# UltraSoundLightConfig.net
KiCad netlist of a schematic drawn in EAGLE
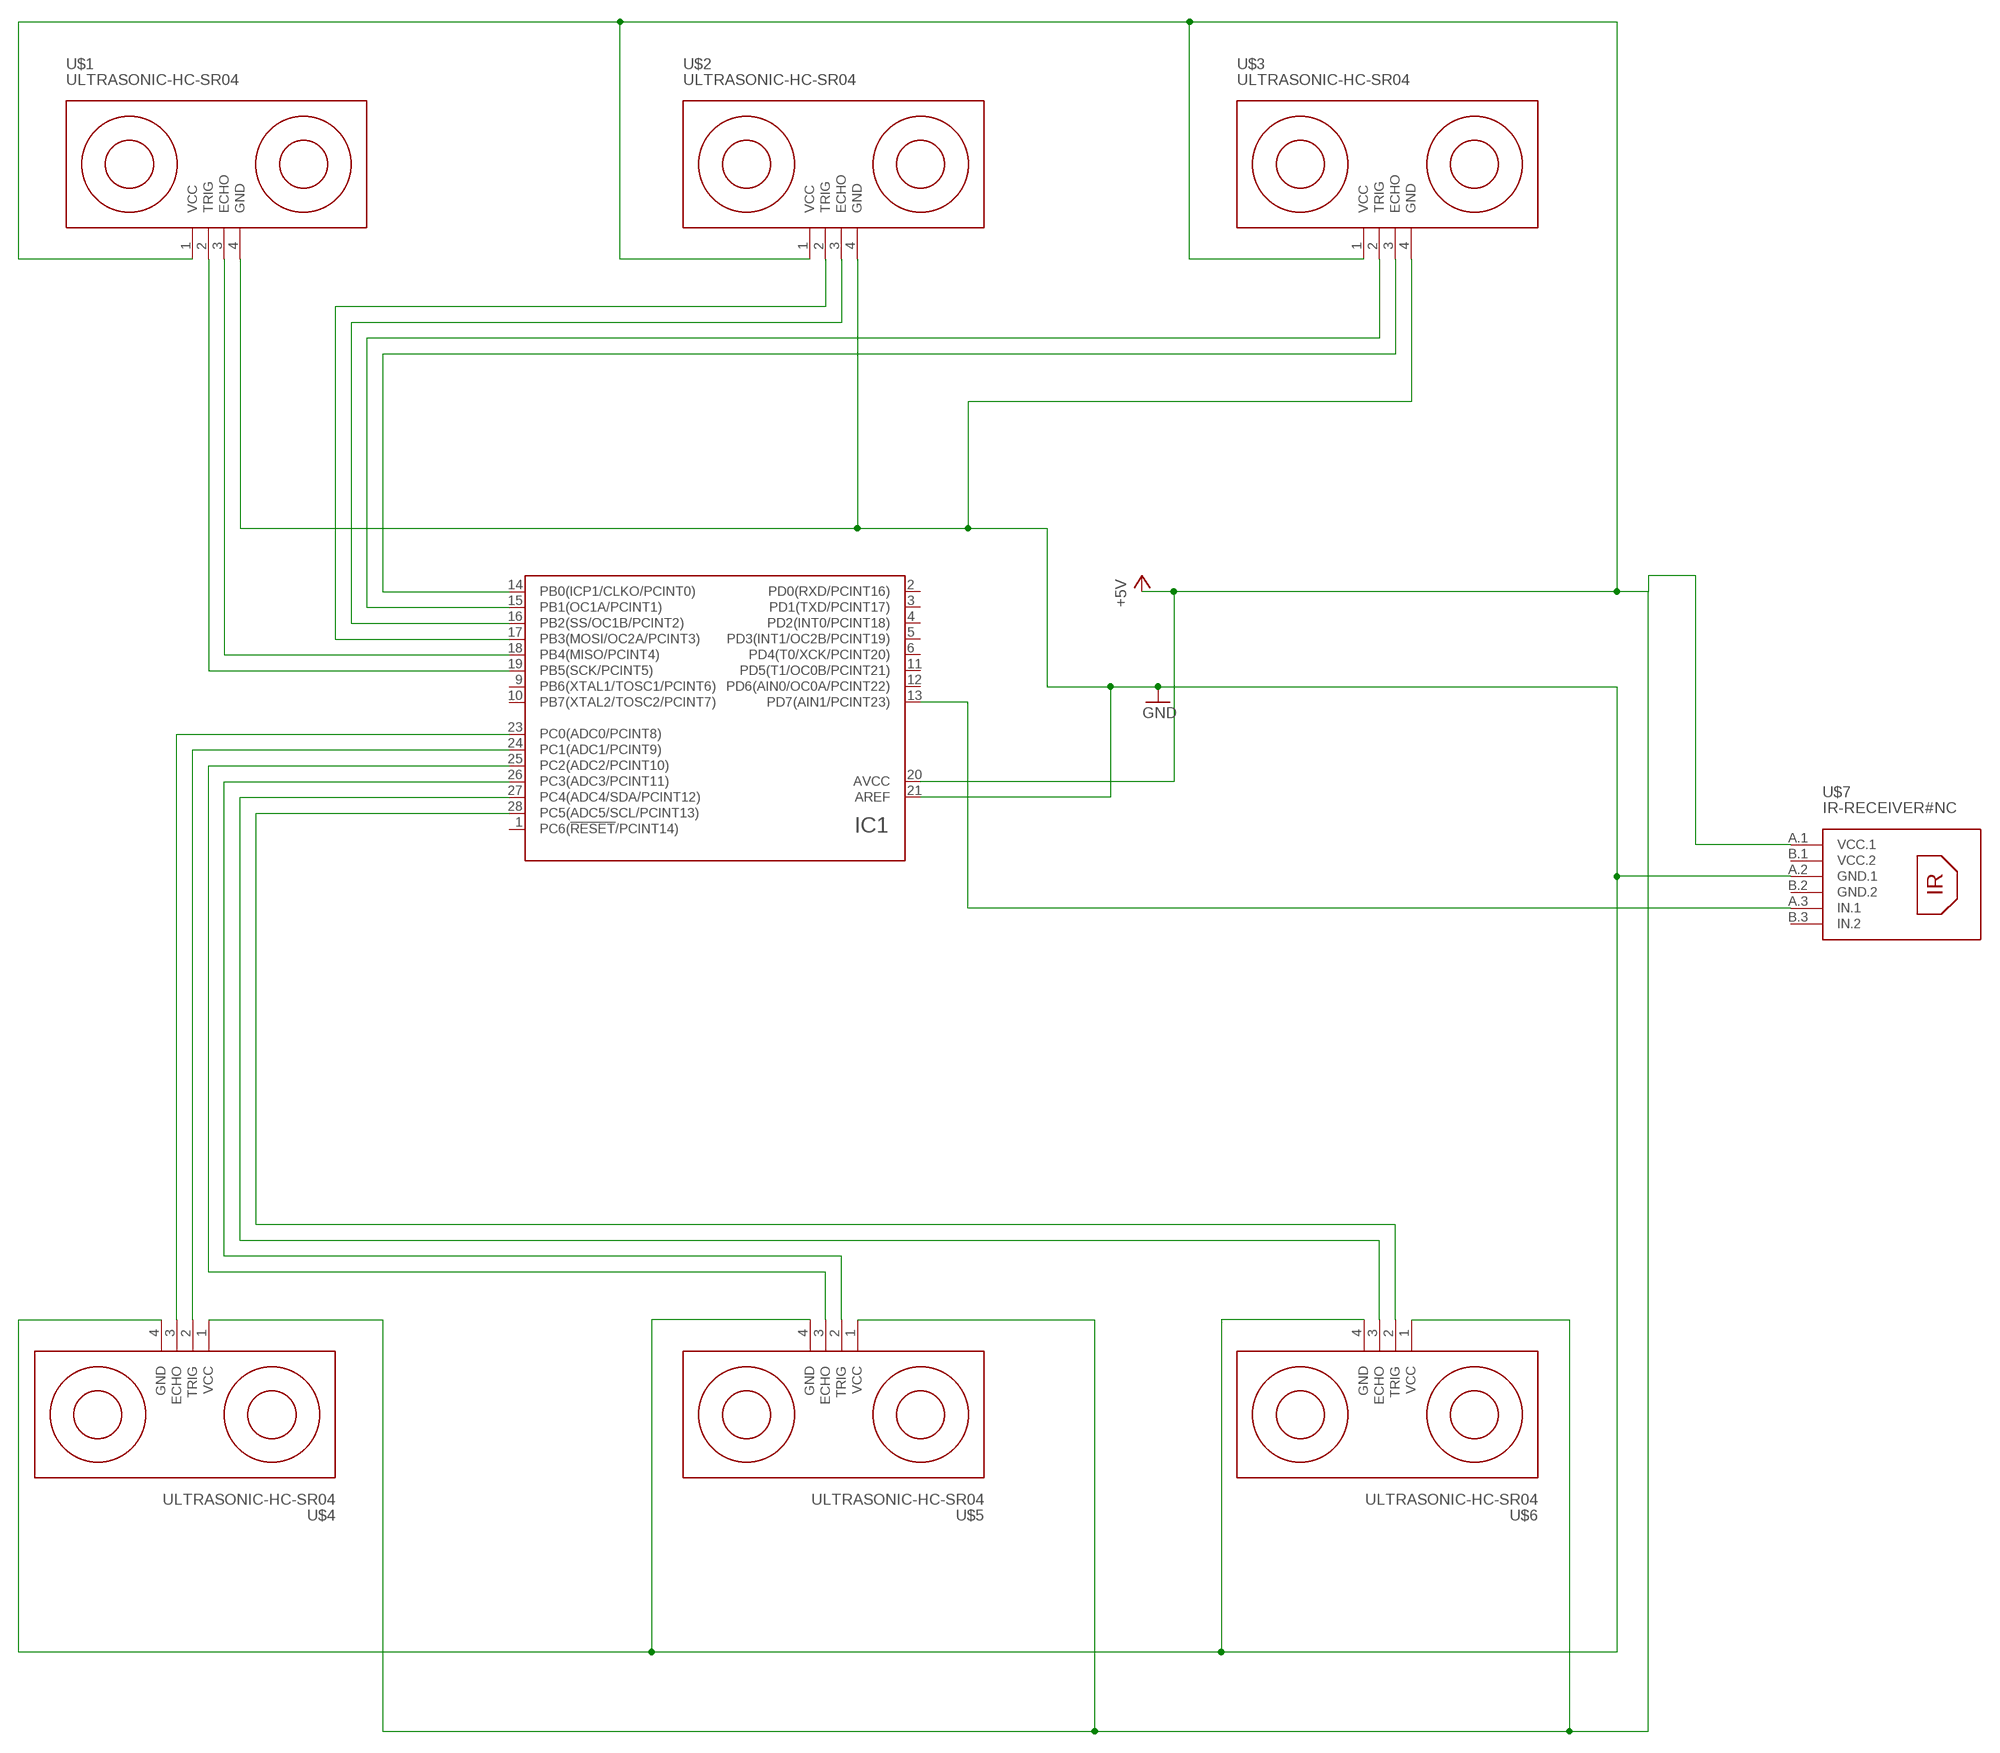
[diagram p0: schematic, sheet 1]

(export (version "E")
  (design (tool "Eeschema 10.0.6"))
  (components
    (comp (ref "IC1")
      (value "ATMEGA48/88/168/328-PU(DIP28)PU")
      (footprint "eagle-import:DIL28")
      (libsource (lib "eagle-import") (part "ATMEGA48/88/168/328-PU(DIP28)PU"))
    )
    (comp (ref "U$1")
      (value "ULTRASONIC-HC-SR04")
      (footprint "eagle-import:ULTRASONIC-HC-SR04")
      (libsource (lib "eagle-import") (part "ULTRASONIC-HC-SR04"))
    )
    (comp (ref "U$2")
      (value "ULTRASONIC-HC-SR04")
      (footprint "eagle-import:ULTRASONIC-HC-SR04")
      (libsource (lib "eagle-import") (part "ULTRASONIC-HC-SR04"))
    )
    (comp (ref "U$3")
      (value "ULTRASONIC-HC-SR04")
      (footprint "eagle-import:ULTRASONIC-HC-SR04")
      (libsource (lib "eagle-import") (part "ULTRASONIC-HC-SR04"))
    )
    (comp (ref "U$4")
      (value "ULTRASONIC-HC-SR04")
      (footprint "eagle-import:ULTRASONIC-HC-SR04")
      (libsource (lib "eagle-import") (part "ULTRASONIC-HC-SR04"))
    )
    (comp (ref "U$5")
      (value "ULTRASONIC-HC-SR04")
      (footprint "eagle-import:ULTRASONIC-HC-SR04")
      (libsource (lib "eagle-import") (part "ULTRASONIC-HC-SR04"))
    )
    (comp (ref "U$6")
      (value "ULTRASONIC-HC-SR04")
      (footprint "eagle-import:ULTRASONIC-HC-SR04")
      (libsource (lib "eagle-import") (part "ULTRASONIC-HC-SR04"))
    )
    (comp (ref "U$7")
      (value "IR-RECEIVER#NC")
      (footprint "eagle-import:IR-RECEIVER#NC")
      (libsource (lib "eagle-import") (part "IR-RECEIVER#NC"))
    )
  )
  (nets
    (net (code "1") (name "+5V") (class "Default")
      (node (ref "IC1") (pin "20") (pinfunction "AVCC_20") (pintype "power_in"))
      (node (ref "U$1") (pin "1") (pinfunction "VCC_1") (pintype "power_in"))
      (node (ref "U$2") (pin "1") (pinfunction "VCC_1") (pintype "power_in"))
      (node (ref "U$3") (pin "1") (pinfunction "VCC_1") (pintype "power_in"))
      (node (ref "U$4") (pin "1") (pinfunction "VCC_1") (pintype "power_in"))
      (node (ref "U$5") (pin "1") (pinfunction "VCC_1") (pintype "power_in"))
      (node (ref "U$6") (pin "1") (pinfunction "VCC_1") (pintype "power_in"))
      (node (ref "U$7") (pin "A.1") (pinfunction "VCC.1_A.1") (pintype "bidirectional"))
    )
    (net (code "2") (name "GND") (class "Default")
      (node (ref "IC1") (pin "21") (pinfunction "AREF_21") (pintype "passive"))
      (node (ref "U$1") (pin "4") (pinfunction "GND_4") (pintype "power_in"))
      (node (ref "U$2") (pin "4") (pinfunction "GND_4") (pintype "power_in"))
      (node (ref "U$3") (pin "4") (pinfunction "GND_4") (pintype "power_in"))
      (node (ref "U$4") (pin "4") (pinfunction "GND_4") (pintype "power_in"))
      (node (ref "U$5") (pin "4") (pinfunction "GND_4") (pintype "power_in"))
      (node (ref "U$6") (pin "4") (pinfunction "GND_4") (pintype "power_in"))
      (node (ref "U$7") (pin "A.2") (pinfunction "GND.1_A.2") (pintype "bidirectional"))
    )
    (net (code "3") (name "Net-(IC1A-PB0(ICP1{slash}CLKO{slash}PCINT0))") (class "Default")
      (node (ref "IC1") (pin "14") (pinfunction "PB0(ICP1/CLKO/PCINT0)_14") (pintype "bidirectional"))
      (node (ref "U$3") (pin "3") (pinfunction "ECHO_3") (pintype "output"))
    )
    (net (code "4") (name "Net-(IC1A-PB1(OC1A{slash}PCINT1))") (class "Default")
      (node (ref "IC1") (pin "15") (pinfunction "PB1(OC1A/PCINT1)_15") (pintype "bidirectional"))
      (node (ref "U$3") (pin "2") (pinfunction "TRIG_2") (pintype "input"))
    )
    (net (code "5") (name "Net-(IC1A-PB2(SS{slash}OC1B{slash}PCINT2))") (class "Default")
      (node (ref "IC1") (pin "16") (pinfunction "PB2(SS/OC1B/PCINT2)_16") (pintype "bidirectional"))
      (node (ref "U$2") (pin "3") (pinfunction "ECHO_3") (pintype "output"))
    )
    (net (code "6") (name "Net-(IC1A-PB3(MOSI{slash}OC2A{slash}PCINT3))") (class "Default")
      (node (ref "IC1") (pin "17") (pinfunction "PB3(MOSI/OC2A/PCINT3)_17") (pintype "bidirectional"))
      (node (ref "U$2") (pin "2") (pinfunction "TRIG_2") (pintype "input"))
    )
    (net (code "7") (name "Net-(IC1A-PB4(MISO{slash}PCINT4))") (class "Default")
      (node (ref "IC1") (pin "18") (pinfunction "PB4(MISO/PCINT4)_18") (pintype "bidirectional"))
      (node (ref "U$1") (pin "3") (pinfunction "ECHO_3") (pintype "output"))
    )
    (net (code "8") (name "Net-(IC1A-PB5(SCK{slash}PCINT5))") (class "Default")
      (node (ref "IC1") (pin "19") (pinfunction "PB5(SCK/PCINT5)_19") (pintype "bidirectional"))
      (node (ref "U$1") (pin "2") (pinfunction "TRIG_2") (pintype "input"))
    )
    (net (code "9") (name "Net-(IC1A-PC0(ADC0{slash}PCINT8))") (class "Default")
      (node (ref "IC1") (pin "23") (pinfunction "PC0(ADC0/PCINT8)_23") (pintype "bidirectional"))
      (node (ref "U$4") (pin "3") (pinfunction "ECHO_3") (pintype "output"))
    )
    (net (code "10") (name "Net-(IC1A-PC1(ADC1{slash}PCINT9))") (class "Default")
      (node (ref "IC1") (pin "24") (pinfunction "PC1(ADC1/PCINT9)_24") (pintype "bidirectional"))
      (node (ref "U$4") (pin "2") (pinfunction "TRIG_2") (pintype "input"))
    )
    (net (code "11") (name "Net-(IC1A-PC2(ADC2{slash}PCINT10))") (class "Default")
      (node (ref "IC1") (pin "25") (pinfunction "PC2(ADC2/PCINT10)_25") (pintype "bidirectional"))
      (node (ref "U$5") (pin "3") (pinfunction "ECHO_3") (pintype "output"))
    )
    (net (code "12") (name "Net-(IC1A-PC3(ADC3{slash}PCINT11))") (class "Default")
      (node (ref "IC1") (pin "26") (pinfunction "PC3(ADC3/PCINT11)_26") (pintype "bidirectional"))
      (node (ref "U$5") (pin "2") (pinfunction "TRIG_2") (pintype "input"))
    )
    (net (code "13") (name "Net-(IC1A-PC4(ADC4{slash}SDA{slash}PCINT12))") (class "Default")
      (node (ref "IC1") (pin "27") (pinfunction "PC4(ADC4/SDA/PCINT12)_27") (pintype "bidirectional"))
      (node (ref "U$6") (pin "3") (pinfunction "ECHO_3") (pintype "output"))
    )
    (net (code "14") (name "Net-(IC1A-PC5(ADC5{slash}SCL{slash}PCINT13))") (class "Default")
      (node (ref "IC1") (pin "28") (pinfunction "PC5(ADC5/SCL/PCINT13)_28") (pintype "bidirectional"))
      (node (ref "U$6") (pin "2") (pinfunction "TRIG_2") (pintype "input"))
    )
    (net (code "15") (name "Net-(IC1A-PD7(AIN1{slash}PCINT23))") (class "Default")
      (node (ref "IC1") (pin "13") (pinfunction "PD7(AIN1/PCINT23)_13") (pintype "bidirectional"))
      (node (ref "U$7") (pin "A.3") (pinfunction "IN.1_A.3") (pintype "bidirectional"))
    )
    (net (code "16") (name "unconnected-(IC1A-PB6(XTAL1{slash}TOSC1{slash}PCINT6)-Pad9)") (class "Default")
      (node (ref "IC1") (pin "9") (pinfunction "PB6(XTAL1/TOSC1/PCINT6)_9") (pintype "bidirectional"))
    )
    (net (code "17") (name "unconnected-(IC1A-PB7(XTAL2{slash}TOSC2{slash}PCINT7)-Pad10)") (class "Default")
      (node (ref "IC1") (pin "10") (pinfunction "PB7(XTAL2/TOSC2/PCINT7)_10") (pintype "bidirectional"))
    )
    (net (code "18") (name "unconnected-(IC1A-PC6(~{RESET}{slash}PCINT14)-Pad1)") (class "Default")
      (node (ref "IC1") (pin "1") (pinfunction "PC6(~{RESET}/PCINT14)_1") (pintype "bidirectional"))
    )
    (net (code "19") (name "unconnected-(IC1A-PD0(RXD{slash}PCINT16)-Pad2)") (class "Default")
      (node (ref "IC1") (pin "2") (pinfunction "PD0(RXD/PCINT16)_2") (pintype "bidirectional"))
    )
    (net (code "20") (name "unconnected-(IC1A-PD1(TXD{slash}PCINT17)-Pad3)") (class "Default")
      (node (ref "IC1") (pin "3") (pinfunction "PD1(TXD/PCINT17)_3") (pintype "bidirectional"))
    )
    (net (code "21") (name "unconnected-(IC1A-PD2(INT0{slash}PCINT18)-Pad4)") (class "Default")
      (node (ref "IC1") (pin "4") (pinfunction "PD2(INT0/PCINT18)_4") (pintype "bidirectional"))
    )
    (net (code "22") (name "unconnected-(IC1A-PD3(INT1{slash}OC2B{slash}PCINT19)-Pad5)") (class "Default")
      (node (ref "IC1") (pin "5") (pinfunction "PD3(INT1/OC2B/PCINT19)_5") (pintype "bidirectional"))
    )
    (net (code "23") (name "unconnected-(IC1A-PD4(T0{slash}XCK{slash}PCINT20)-Pad6)") (class "Default")
      (node (ref "IC1") (pin "6") (pinfunction "PD4(T0/XCK/PCINT20)_6") (pintype "bidirectional"))
    )
    (net (code "24") (name "unconnected-(IC1A-PD5(T1{slash}OC0B{slash}PCINT21)-Pad11)") (class "Default")
      (node (ref "IC1") (pin "11") (pinfunction "PD5(T1/OC0B/PCINT21)_11") (pintype "bidirectional"))
    )
    (net (code "25") (name "unconnected-(IC1A-PD6(AIN0{slash}OC0A{slash}PCINT22)-Pad12)") (class "Default")
      (node (ref "IC1") (pin "12") (pinfunction "PD6(AIN0/OC0A/PCINT22)_12") (pintype "bidirectional"))
    )
    (net (code "26") (name "unconnected-(U$7-GND.2-PadB.2)") (class "Default")
      (node (ref "U$7") (pin "B.2") (pinfunction "GND.2_B.2") (pintype "bidirectional"))
    )
    (net (code "27") (name "unconnected-(U$7-IN.2-PadB.3)") (class "Default")
      (node (ref "U$7") (pin "B.3") (pinfunction "IN.2_B.3") (pintype "bidirectional"))
    )
    (net (code "28") (name "unconnected-(U$7-VCC.2-PadB.1)") (class "Default")
      (node (ref "U$7") (pin "B.1") (pinfunction "VCC.2_B.1") (pintype "bidirectional"))
    )
  )
)
